# I2C_Multiplexer.net
KiCad netlist of a schematic drawn in Altium Designer
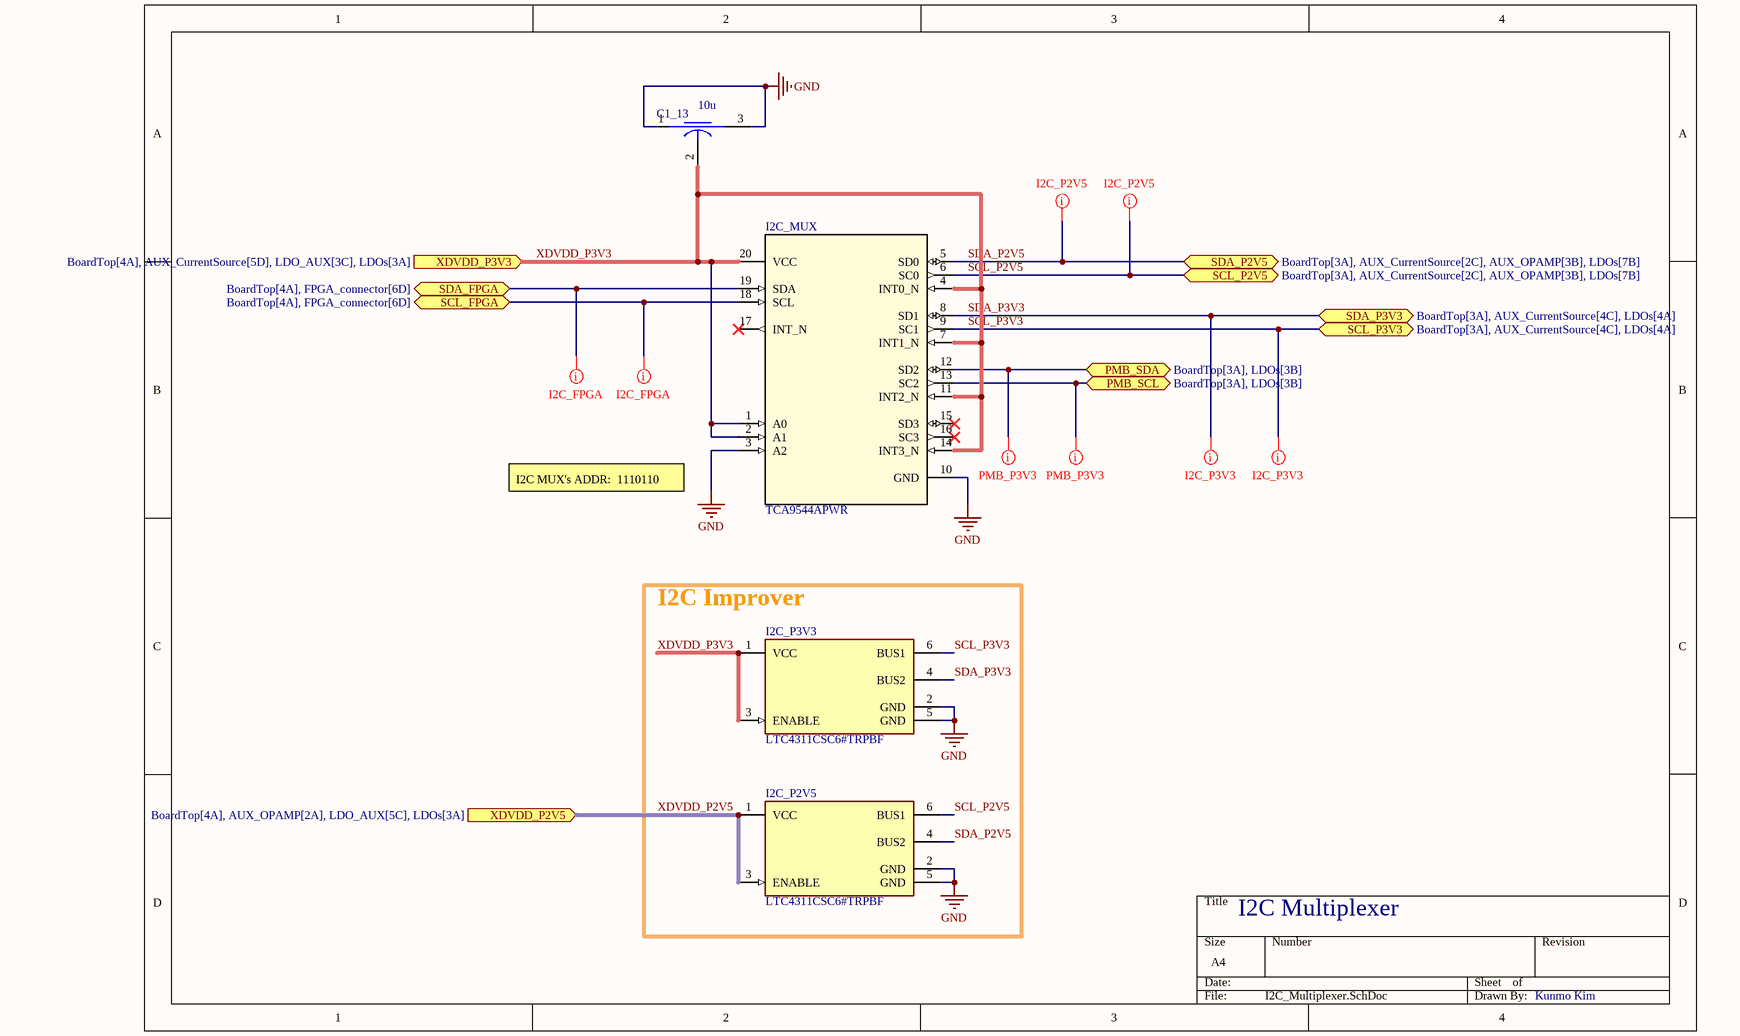
[diagram p0: I2C_Multiplexer.SchDoc]

(export (version "E")
  (design (tool "Eeschema 10.0.6"))
  (components
    (comp (ref "C1_13")
      (value "10u")
      (footprint "FP-NFM15-0_2-MFG")
      (description "CAP FEEDTHRU")
      (libsource (lib "Altium Content Vault") (part "0d6e7657c98936515f4dd3c3b322889"))
    )
    (comp (ref "I2C_MUX")
      (value "TCA9544APWR")
      (footprint "PW0020A_L")
      (description "No Description Available")
      (fields (field (name "MANUFACTURER") "Texas Instruments"))
      (libsource (lib "TCA9544APWR") (part "TCA9544APWR"))
    )
    (comp (ref "I2C_P2V5")
      (value "LTC4311CSC6#TRPBF")
      (footprint "FP-SC6-6-05-08-1638-IPC_B")
      (description "IC POWER MANAGEMENT")
      (libsource (lib "LTC4311") (part "CMP-09093-000026-1"))
    )
    (comp (ref "I2C_P3V3")
      (value "LTC4311CSC6#TRPBF")
      (footprint "FP-SC6-6-05-08-1638-IPC_B")
      (description "IC POWER MANAGEMENT")
      (libsource (lib "LTC4311") (part "CMP-09093-000026-1"))
    )
  )
  (nets
    (net (code "1") (name "/PMB_SCL") (class "Default")
      (node (ref "I2C_MUX") (pin "13") (pinfunction "SC2_13") (pintype "output"))
    )
    (net (code "2") (name "/PMB_SDA") (class "Default")
      (node (ref "I2C_MUX") (pin "12") (pinfunction "SD2_12") (pintype "bidirectional"))
    )
    (net (code "3") (name "/SCL_FPGA") (class "Default")
      (node (ref "I2C_MUX") (pin "18") (pinfunction "SCL_18") (pintype "input"))
    )
    (net (code "4") (name "/SCL_P2V5") (class "Default")
      (node (ref "I2C_MUX") (pin "6") (pinfunction "SC0_6") (pintype "output"))
      (node (ref "I2C_P2V5") (pin "6") (pinfunction "BUS1_6") (pintype "passive"))
    )
    (net (code "5") (name "/SCL_P3V3") (class "Default")
      (node (ref "I2C_MUX") (pin "9") (pinfunction "SC1_9") (pintype "output"))
      (node (ref "I2C_P3V3") (pin "6") (pinfunction "BUS1_6") (pintype "passive"))
    )
    (net (code "6") (name "/SDA_FPGA") (class "Default")
      (node (ref "I2C_MUX") (pin "19") (pinfunction "SDA_19") (pintype "input"))
    )
    (net (code "7") (name "/SDA_P2V5") (class "Default")
      (node (ref "I2C_MUX") (pin "5") (pinfunction "SD0_5") (pintype "bidirectional"))
      (node (ref "I2C_P2V5") (pin "4") (pinfunction "BUS2_4") (pintype "passive"))
    )
    (net (code "8") (name "/SDA_P3V3") (class "Default")
      (node (ref "I2C_MUX") (pin "8") (pinfunction "SD1_8") (pintype "bidirectional"))
      (node (ref "I2C_P3V3") (pin "4") (pinfunction "BUS2_4") (pintype "passive"))
    )
    (net (code "9") (name "/XDVDD_P2V5") (class "Default")
      (node (ref "I2C_P2V5") (pin "1") (pinfunction "VCC_1") (pintype "power_in"))
      (node (ref "I2C_P2V5") (pin "3") (pinfunction "ENABLE_3") (pintype "input"))
    )
    (net (code "10") (name "/XDVDD_P3V3") (class "Default")
      (node (ref "C1_13") (pin "2") (pinfunction "GND_2") (pintype "passive"))
      (node (ref "I2C_MUX") (pin "1") (pinfunction "A0_1") (pintype "input"))
      (node (ref "I2C_MUX") (pin "11") (pinfunction "INT2_N_11") (pintype "input"))
      (node (ref "I2C_MUX") (pin "14") (pinfunction "INT3_N_14") (pintype "input"))
      (node (ref "I2C_MUX") (pin "2") (pinfunction "A1_2") (pintype "input"))
      (node (ref "I2C_MUX") (pin "20") (pinfunction "VCC_20") (pintype "power_in"))
      (node (ref "I2C_MUX") (pin "4") (pinfunction "INT0_N_4") (pintype "input"))
      (node (ref "I2C_MUX") (pin "7") (pinfunction "INT1_N_7") (pintype "input"))
      (node (ref "I2C_P3V3") (pin "1") (pinfunction "VCC_1") (pintype "power_in"))
      (node (ref "I2C_P3V3") (pin "3") (pinfunction "ENABLE_3") (pintype "input"))
    )
    (net (code "11") (name "GND") (class "Default")
      (node (ref "C1_13") (pin "1") (pinfunction "Input_1") (pintype "passive"))
      (node (ref "C1_13") (pin "3") (pinfunction "Output_3") (pintype "passive"))
      (node (ref "I2C_MUX") (pin "10") (pinfunction "GND_10") (pintype "power_in"))
      (node (ref "I2C_MUX") (pin "3") (pinfunction "A2_3") (pintype "input"))
      (node (ref "I2C_P2V5") (pin "2") (pinfunction "GND_2") (pintype "power_in"))
      (node (ref "I2C_P2V5") (pin "5") (pinfunction "GND_5") (pintype "power_in"))
      (node (ref "I2C_P3V3") (pin "2") (pinfunction "GND_2") (pintype "power_in"))
      (node (ref "I2C_P3V3") (pin "5") (pinfunction "GND_5") (pintype "power_in"))
    )
    (net (code "12") (name "unconnected-(I2C_MUX-INT_N-Pad17)") (class "Default")
      (node (ref "I2C_MUX") (pin "17") (pinfunction "INT_N_17") (pintype "output+no_connect"))
    )
    (net (code "13") (name "unconnected-(I2C_MUX-SC3-Pad16)") (class "Default")
      (node (ref "I2C_MUX") (pin "16") (pinfunction "SC3_16") (pintype "output+no_connect"))
    )
    (net (code "14") (name "unconnected-(I2C_MUX-SD3-Pad15)") (class "Default")
      (node (ref "I2C_MUX") (pin "15") (pinfunction "SD3_15") (pintype "bidirectional+no_connect"))
    )
  )
)
